# fabflash-mk-2_1-controller.net
KiCad netlist of a schematic drawn in EAGLE
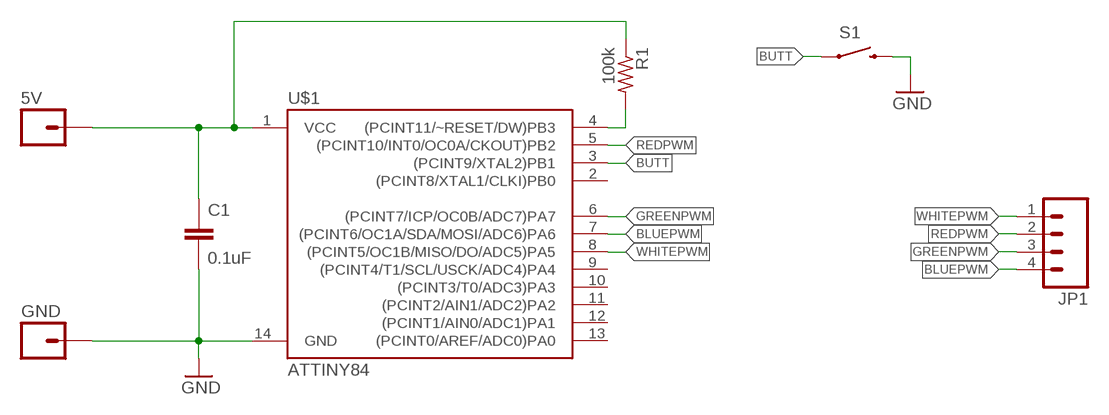
[diagram p0: schematic, sheet 1]

(export (version "E")
  (design (tool "Eeschema 10.0.6"))
  (components
    (comp (ref "5V")
      (value "M01PTH-0.9MM")
      (footprint "eagle-import:1X01-0.9MM")
      (libsource (lib "eagle-import") (part "M01PTH-0.9MM"))
    )
    (comp (ref "C1")
      (value "0.1uF")
      (footprint "eagle-import:C0603")
      (libsource (lib "eagle-import") (part "CAPACITOR-CERAMICC0603"))
    )
    (comp (ref "GND")
      (value "M01PTH-0.9MM")
      (footprint "eagle-import:1X01-0.9MM")
      (libsource (lib "eagle-import") (part "M01PTH-0.9MM"))
    )
    (comp (ref "JP1")
      (value "M04JST-PTH-VERT")
      (footprint "eagle-import:JST-4-PH-VERT-PTH")
      (libsource (lib "eagle-import") (part "M04JST-PTH-VERT"))
    )
    (comp (ref "R1")
      (value "100k")
      (footprint "eagle-import:R0603")
      (libsource (lib "eagle-import") (part "RESISTORR0603"))
    )
    (comp (ref "S1")
      (value "SWITCH-MOMENTARY-212MM")
      (footprint "eagle-import:TACTILE-PTH-12MM")
      (libsource (lib "eagle-import") (part "SWITCH-MOMENTARY-212MM"))
    )
    (comp (ref "U$1")
      (value "ATTINY84")
      (footprint "eagle-import:SO14")
      (libsource (lib "eagle-import") (part "ATTINY84"))
    )
  )
  (nets
    (net (code "1") (name "BLUEPWM") (class "Default")
      (node (ref "JP1") (pin "4") (pinfunction "4_4") (pintype "passive"))
      (node (ref "U$1") (pin "7") (pinfunction "(PCINT6/OC1A/SDA/MOSI/ADC6)PA6_7") (pintype "bidirectional"))
    )
    (net (code "2") (name "BUTT") (class "Default")
      (node (ref "S1") (pin "1") (pinfunction "1_1") (pintype "passive"))
      (node (ref "U$1") (pin "3") (pinfunction "(PCINT9/XTAL2)PB1_3") (pintype "bidirectional"))
    )
    (net (code "3") (name "GND") (class "Default")
      (node (ref "C1") (pin "2") (pinfunction "2_2") (pintype "passive"))
      (node (ref "GND") (pin "1") (pinfunction "1_1") (pintype "passive"))
      (node (ref "S1") (pin "3") (pinfunction "2_3") (pintype "passive"))
      (node (ref "U$1") (pin "14") (pinfunction "GND_14") (pintype "bidirectional"))
    )
    (net (code "4") (name "GREENPWM") (class "Default")
      (node (ref "JP1") (pin "3") (pinfunction "3_3") (pintype "passive"))
      (node (ref "U$1") (pin "6") (pinfunction "(PCINT7/ICP/OC0B/ADC7)PA7_6") (pintype "bidirectional"))
    )
    (net (code "5") (name "Net-(U$1-(PCINT11{slash}~{RESET{slash}DW})PB3)") (class "Default")
      (node (ref "R1") (pin "2") (pinfunction "2_2") (pintype "passive"))
      (node (ref "U$1") (pin "4") (pinfunction "(PCINT11/~{RESET/DW})PB3_4") (pintype "bidirectional"))
    )
    (net (code "6") (name "Net-(U$1-VCC)") (class "Default")
      (node (ref "5V") (pin "1") (pinfunction "1_1") (pintype "passive"))
      (node (ref "C1") (pin "1") (pinfunction "1_1") (pintype "passive"))
      (node (ref "R1") (pin "1") (pinfunction "1_1") (pintype "passive"))
      (node (ref "U$1") (pin "1") (pinfunction "VCC_1") (pintype "bidirectional"))
    )
    (net (code "7") (name "REDPWM") (class "Default")
      (node (ref "JP1") (pin "2") (pinfunction "2_2") (pintype "passive"))
      (node (ref "U$1") (pin "5") (pinfunction "(PCINT10/INT0/OC0A/CKOUT)PB2_5") (pintype "bidirectional"))
    )
    (net (code "8") (name "WHITEPWM") (class "Default")
      (node (ref "JP1") (pin "1") (pinfunction "1_1") (pintype "passive"))
      (node (ref "U$1") (pin "8") (pinfunction "(PCINT5/OC1B/MISO/DO/ADC5)PA5_8") (pintype "bidirectional"))
    )
    (net (code "9") (name "unconnected-(U$1-(PCINT0{slash}AREF{slash}ADC0)PA0-Pad13)") (class "Default")
      (node (ref "U$1") (pin "13") (pinfunction "(PCINT0/AREF/ADC0)PA0_13") (pintype "bidirectional"))
    )
    (net (code "10") (name "unconnected-(U$1-(PCINT1{slash}AIN0{slash}ADC1)PA1-Pad12)") (class "Default")
      (node (ref "U$1") (pin "12") (pinfunction "(PCINT1/AIN0/ADC1)PA1_12") (pintype "bidirectional"))
    )
    (net (code "11") (name "unconnected-(U$1-(PCINT2{slash}AIN1{slash}ADC2)PA2-Pad11)") (class "Default")
      (node (ref "U$1") (pin "11") (pinfunction "(PCINT2/AIN1/ADC2)PA2_11") (pintype "bidirectional"))
    )
    (net (code "12") (name "unconnected-(U$1-(PCINT3{slash}T0{slash}ADC3)PA3-Pad10)") (class "Default")
      (node (ref "U$1") (pin "10") (pinfunction "(PCINT3/T0/ADC3)PA3_10") (pintype "bidirectional"))
    )
    (net (code "13") (name "unconnected-(U$1-(PCINT4{slash}T1{slash}SCL{slash}USCK{slash}ADC4)PA4-Pad9)") (class "Default")
      (node (ref "U$1") (pin "9") (pinfunction "(PCINT4/T1/SCL/USCK/ADC4)PA4_9") (pintype "bidirectional"))
    )
    (net (code "14") (name "unconnected-(U$1-(PCINT8{slash}XTAL1{slash}CLKI)PB0-Pad2)") (class "Default")
      (node (ref "U$1") (pin "2") (pinfunction "(PCINT8/XTAL1/CLKI)PB0_2") (pintype "bidirectional"))
    )
  )
)
